# Power_VCC3V3.net
KiCad netlist of a schematic drawn in Altium Designer
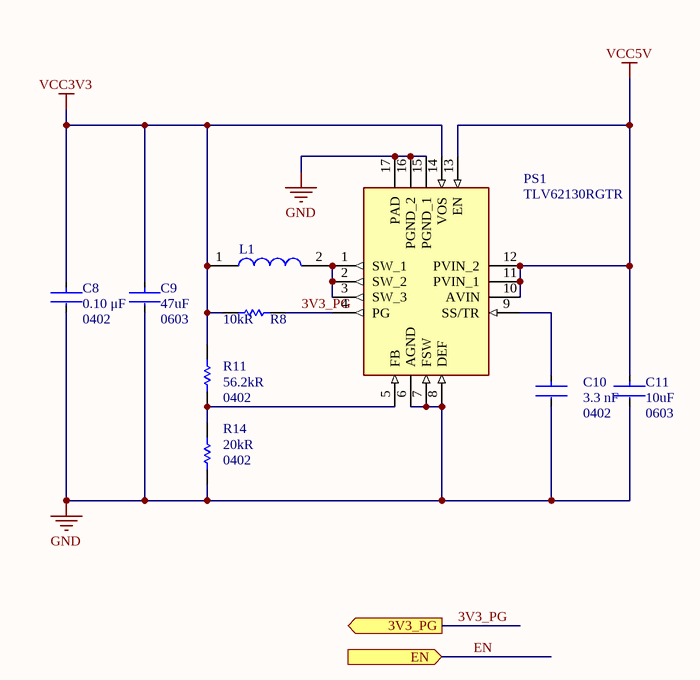
[diagram p0: Power_VCC3V3.SchDoc]

(export (version "E")
  (design (tool "Eeschema 10.0.6"))
  (components
    (comp (ref "C8")
      (value "0.10 μF")
      (footprint "FP-C0402-BB-MFG")
      (description "CAP CER 0.1UF 10V X5R 0402")
      (fields
        (field (name "MANUFACTURER") "Kemet")
        (field (name "TOLERANCE") "0.1")
        (field (name "CASE/PACKAGE") "0402")
      )
      (libsource (lib "Altium Content Vault") (part "b4654b650e69147ec39a6b967a45e02"))
    )
    (comp (ref "C9")
      (value "47uF")
      (footprint "FP-GRM188-0_2-IPC_B")
      (description "Chip Multilayer Ceramic Capacitors for General Purpose, 0603, 47uF, X5R, 15%, 20%, 6.3V")
      (fields
        (field (name "CASE CODE (IMPERIAL)") "0603")
        (field (name "TOLERANCE") "20%")
        (field (name "MANUFACTURER") "Murata")
      )
      (libsource (lib "Altium Content Vault") (part "11868f565c42a9108669ba33697ecf6"))
    )
    (comp (ref "C10")
      (value "3.3 nF")
      (footprint "FP-CC0402-MFG")
      (description "CAP CER 3300PF 50V X7R 0402")
      (fields
        (field (name "OCTOPART") "https://octopart.com/cc0402krx7r9bb332-yageo-192887")
        (field (name "MANUFACTURER") "YAGEO")
        (field (name "CASE/PACKAGE") "0402")
      )
      (libsource (lib "Altium Content Vault") (part "11868f565c42a9108669ba33697ecf6"))
    )
    (comp (ref "C11")
      (value "10uF")
      (footprint "FP-GRM188-0_1-e0_2_0_55-IPC_A")
      (description "Chip Multilayer Ceramic Capacitors for General Purpose, 0603, 10uF, X5R, 15%, 20%, 6.3V")
      (fields
        (field (name "CASE/PACKAGE") "0603")
        (field (name "VOLTAGE") "6.3V")
        (field (name "TOLERANCE") "20%")
      )
      (libsource (lib "Altium Content Vault") (part "02cd4be3c70576c341d710602a673aa"))
    )
    (comp (ref "L1")
      (value "252012CDMCDS2R2MC")
      (footprint "INDPM2520X120N")
      (description "Inductor")
      (fields (field (name "MANUFACTURER_PART_NUMBER") "252012CDMCDS‐2R2MC"))
      (libsource (lib "CCZynq") (part "252012CDMCDS2R2MC"))
    )
    (comp (ref "PS1")
      (value "TLV62130RGTR")
      (footprint "FP-RGT0016C-MFG")
      (description "Buck Switching Regulator IC Positive Adjustable 0.9V 1 Output 3A 16-VFQFN Exposed Pad")
      (fields
        (field (name "MOUSER PART NUMBER") "595-TLV62130RGTR")
        (field (name "MANUFACTURER") "Texas Instruments")
      )
      (libsource (lib "HamedLib") (part "TLV62130RGTR"))
    )
    (comp (ref "R8")
      (value "10kR")
      (footprint "RESC1005X40X25LL05T10")
      (description "10K 0402 1% 1/16W +-100PPM")
      (fields (field (name "PART NUMBER") "RC0402FR-0710KL") (field (name "MANUFACTURER") "Yageo / Phycomp"))
      (libsource (lib "Altium Content Vault") (part "RES"))
    )
    (comp (ref "R11")
      (value "56.2kR")
      (footprint "RESC1005X40X25NL05T05")
      (fields
        (field (name "PART NUMBER") "CRCW040256K2FKED")
        (field (name "MANUFACTURER") "Vishay Dale")
        (field (name "CASE/PACKAGE") "0402")
        (field (name "TOLERANCE") "1%")
      )
      (libsource (lib "Altium Content Vault") (part "RES"))
    )
    (comp (ref "R14")
      (value "20kR")
      (footprint "RESC1005X40X25NL05T10")
      (fields
        (field (name "PART NUMBER") "RC0402FR-0720KL")
        (field (name "MANUFACTURER") "Yageo / Phycomp")
        (field (name "CASE/PACKAGE") "0402")
        (field (name "TOLERANCE") "1%")
      )
      (libsource (lib "Altium Content Vault") (part "RES"))
    )
  )
  (nets
    (net (code "1") (name "/3V3_PG") (class "Default")
      (node (ref "PS1") (pin "4") (pinfunction "PG_4") (pintype "output"))
      (node (ref "R8") (pin "2") (pinfunction "2_2") (pintype "passive"))
    )
    (net (code "3") (name "GND") (class "Default")
      (node (ref "C10") (pin "2") (pinfunction "2_2") (pintype "passive"))
      (node (ref "C11") (pin "2") (pinfunction "2_2") (pintype "passive"))
      (node (ref "C8") (pin "2") (pinfunction "2_2") (pintype "passive"))
      (node (ref "C9") (pin "2") (pinfunction "2_2") (pintype "passive"))
      (node (ref "PS1") (pin "15") (pinfunction "PGND_1_15") (pintype "power_in"))
      (node (ref "PS1") (pin "16") (pinfunction "PGND_2_16") (pintype "power_in"))
      (node (ref "PS1") (pin "17") (pinfunction "PAD_17") (pintype "power_in"))
      (node (ref "PS1") (pin "6") (pinfunction "AGND_6") (pintype "power_in"))
      (node (ref "PS1") (pin "7") (pinfunction "FSW_7") (pintype "input"))
      (node (ref "PS1") (pin "8") (pinfunction "DEF_8") (pintype "input"))
      (node (ref "R14") (pin "1") (pinfunction "1_1") (pintype "passive"))
    )
    (net (code "4") (name "Net-(PS1-FB)") (class "Default")
      (node (ref "PS1") (pin "5") (pinfunction "FB_5") (pintype "input"))
      (node (ref "R11") (pin "1") (pinfunction "1_1") (pintype "passive"))
      (node (ref "R14") (pin "2") (pinfunction "2_2") (pintype "passive"))
    )
    (net (code "5") (name "Net-(PS1-SS{slash}TR)") (class "Default")
      (node (ref "C10") (pin "1") (pinfunction "1_1") (pintype "passive"))
      (node (ref "PS1") (pin "9") (pinfunction "SS/TR_9") (pintype "input"))
    )
    (net (code "6") (name "Net-(PS1-SW_1)") (class "Default")
      (node (ref "L1") (pin "2") (pinfunction "2_2") (pintype "passive"))
      (node (ref "PS1") (pin "1") (pinfunction "SW_1_1") (pintype "output"))
      (node (ref "PS1") (pin "2") (pinfunction "SW_2_2") (pintype "output"))
      (node (ref "PS1") (pin "3") (pinfunction "SW_3_3") (pintype "output"))
    )
    (net (code "7") (name "VCC3V3") (class "Default")
      (node (ref "C8") (pin "1") (pinfunction "1_1") (pintype "passive"))
      (node (ref "C9") (pin "1") (pinfunction "1_1") (pintype "passive"))
      (node (ref "L1") (pin "1") (pinfunction "1_1") (pintype "passive"))
      (node (ref "PS1") (pin "14") (pinfunction "VOS_14") (pintype "input"))
      (node (ref "R11") (pin "2") (pinfunction "2_2") (pintype "passive"))
      (node (ref "R8") (pin "1") (pinfunction "1_1") (pintype "passive"))
    )
    (net (code "8") (name "VCC5V") (class "Default")
      (node (ref "C11") (pin "1") (pinfunction "1_1") (pintype "passive"))
      (node (ref "PS1") (pin "10") (pinfunction "AVIN_10") (pintype "power_in"))
      (node (ref "PS1") (pin "11") (pinfunction "PVIN_1_11") (pintype "power_in"))
      (node (ref "PS1") (pin "12") (pinfunction "PVIN_2_12") (pintype "power_in"))
      (node (ref "PS1") (pin "13") (pinfunction "EN_13") (pintype "input"))
    )
  )
)
